# Motor_PowerMosfet.net
KiCad netlist of a schematic drawn in Altium Designer
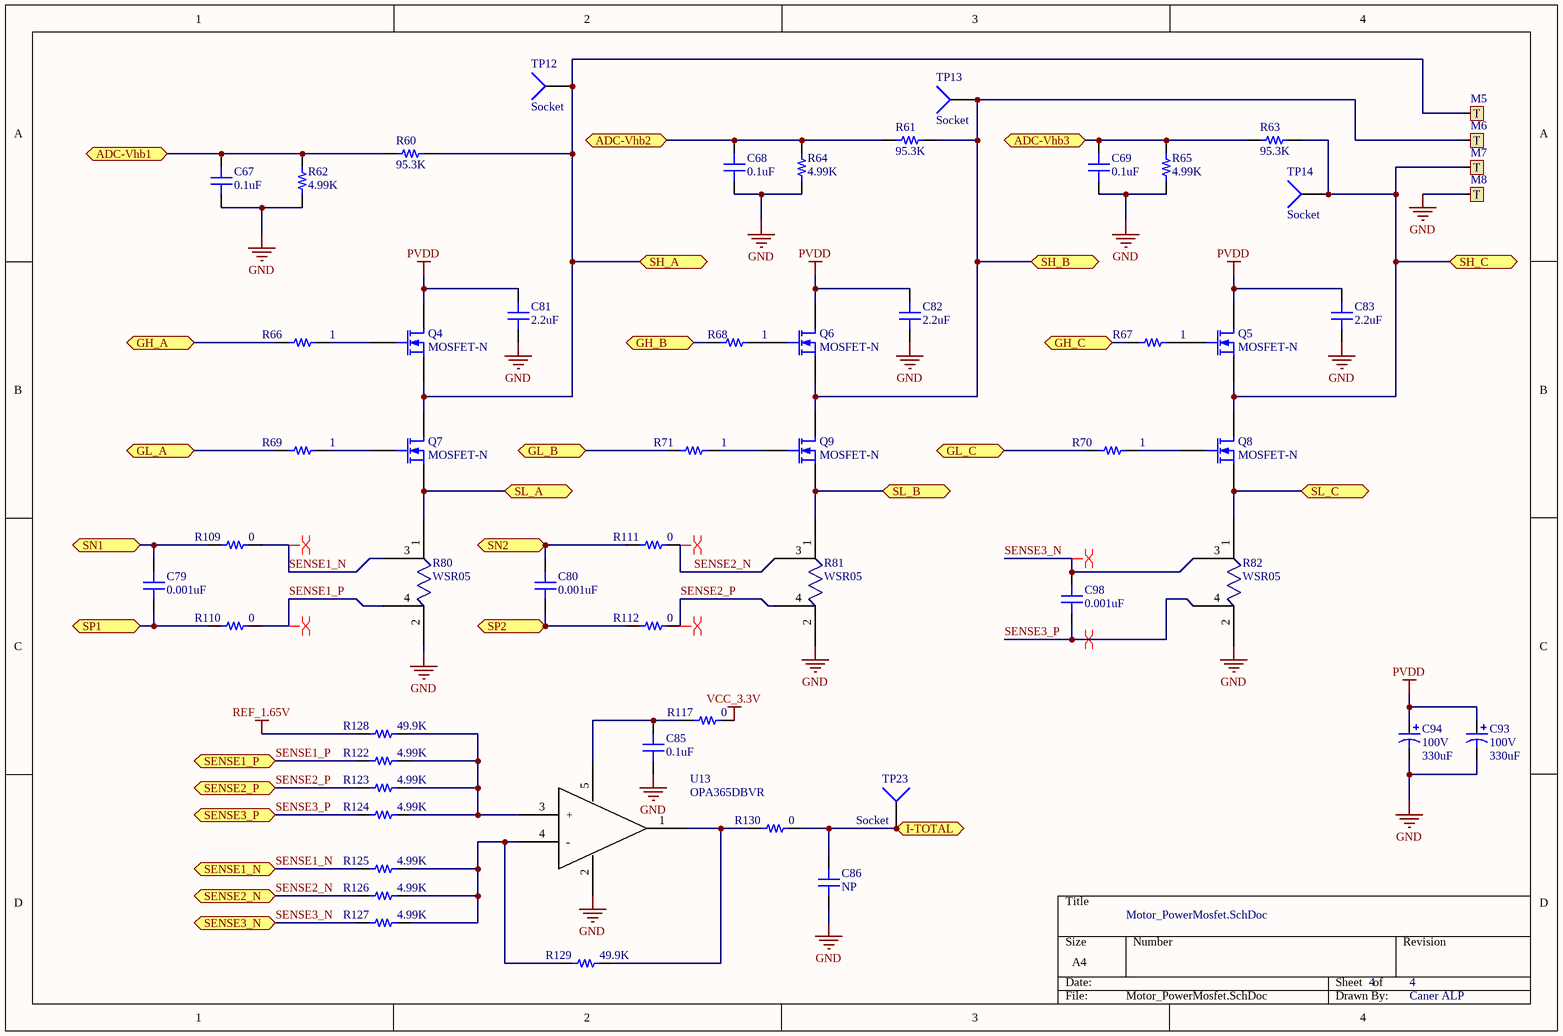
[diagram p0: Motor_PowerMosfet.SchDoc]

(export (version "E")
  (design (tool "Eeschema 10.0.6"))
  (components
    (comp (ref "C67")
      (value "0.1uF")
      (footprint "CAP 0603/1608")
      (description "CAP CER 0.1UF 16V X7R 0603")
      (fields (field (name "PART NUMBER") "CC0603KPX7R7BB104") (field (name "MANUFACTURER") "Yageo"))
      (libsource (lib "Celestial Library Database") (part "Capacitor"))
    )
    (comp (ref "C68")
      (value "0.1uF")
      (footprint "CAP 0603/1608")
      (description "CAP CER 0.1UF 16V X7R 0603")
      (fields (field (name "PART NUMBER") "CC0603KPX7R7BB104") (field (name "MANUFACTURER") "Yageo"))
      (libsource (lib "Celestial Library Database") (part "Capacitor"))
    )
    (comp (ref "C69")
      (value "0.1uF")
      (footprint "CAP 0603/1608")
      (description "CAP CER 0.1UF 16V X7R 0603")
      (fields (field (name "PART NUMBER") "CC0603KPX7R7BB104") (field (name "MANUFACTURER") "Yageo"))
      (libsource (lib "Celestial Library Database") (part "Capacitor"))
    )
    (comp (ref "C79")
      (value "0.001uF")
      (footprint "CAP 0603/1608")
      (description "CAP CER 0.1UF 16V X7R 0603")
      (fields (field (name "PART NUMBER") "CC0603KPX7R7BB104") (field (name "MANUFACTURER") "Yageo"))
      (libsource (lib "Celestial Library Database") (part "Capacitor"))
    )
    (comp (ref "C80")
      (value "0.001uF")
      (footprint "CAP 0603/1608")
      (description "CAP CER 0.1UF 16V X7R 0603")
      (fields (field (name "PART NUMBER") "CC0603KPX7R7BB104") (field (name "MANUFACTURER") "Yageo"))
      (libsource (lib "Celestial Library Database") (part "Capacitor"))
    )
    (comp (ref "C81")
      (value "2.2uF")
      (footprint "CAP 1210/3225 - 2.5MM")
      (description "CAP CER 2.2UF 100V X7R 1210")
      (fields
        (field (name "PART NUMBER") "C3225X7R2A225K230AM")
        (field (name "MANUFACTURER") "TDK Corporation")
      )
      (libsource (lib "Celestial Library Database") (part "Capacitor"))
    )
    (comp (ref "C82")
      (value "2.2uF")
      (footprint "CAP 1210/3225 - 2.5MM")
      (description "CAP CER 2.2UF 100V X7R 1210")
      (fields
        (field (name "PART NUMBER") "C3225X7R2A225K230AM")
        (field (name "MANUFACTURER") "TDK Corporation")
      )
      (libsource (lib "Celestial Library Database") (part "Capacitor"))
    )
    (comp (ref "C83")
      (value "2.2uF")
      (footprint "CAP 1210/3225 - 2.5MM")
      (description "CAP CER 2.2UF 100V X7R 1210")
      (fields
        (field (name "PART NUMBER") "C3225X7R2A225K230AM")
        (field (name "MANUFACTURER") "TDK Corporation")
      )
      (libsource (lib "Celestial Library Database") (part "Capacitor"))
    )
    (comp (ref "C85")
      (value "0.1uF")
      (footprint "CAP 0603/1608")
      (description "CAP CER 0.1UF 16V X7R 0603")
      (fields (field (name "PART NUMBER") "CC0603KPX7R7BB104") (field (name "MANUFACTURER") "Yageo"))
      (libsource (lib "Celestial Library Database") (part "Capacitor"))
    )
    (comp (ref "C86")
      (value "NP")
      (footprint "CAP 0603/1608")
      (description "CAP CER 0.1UF 16V X7R 0603")
      (fields (field (name "PART NUMBER") "CC0603KPX7R7BB104") (field (name "MANUFACTURER") "Yageo"))
      (libsource (lib "Celestial Library Database") (part "Capacitor"))
    )
    (comp (ref "C93")
      (value "100V")
      (footprint "RB7.6-15")
      (description "Polarized Capacitor (Radial)")
      (fields (field (name "ALTIUM_VALUE") "330uF") (field (name "PUBLISHER") "Altium Limited"))
      (libsource (lib "Miscellaneous Devices") (part "Cap Pol1"))
    )
    (comp (ref "C94")
      (value "100V")
      (footprint "RB7.6-15")
      (description "Polarized Capacitor (Radial)")
      (fields (field (name "ALTIUM_VALUE") "330uF") (field (name "PUBLISHER") "Altium Limited"))
      (libsource (lib "Miscellaneous Devices") (part "Cap Pol1"))
    )
    (comp (ref "C98")
      (value "0.001uF")
      (footprint "CAP 0603/1608")
      (description "CAP CER 0.1UF 16V X7R 0603")
      (fields (field (name "PART NUMBER") "CC0603KPX7R7BB104") (field (name "MANUFACTURER") "Yageo"))
      (libsource (lib "Celestial Library Database") (part "Capacitor"))
    )
    (comp (ref "M5") (value "Conn") (footprint "M5 Nut") (libsource (lib "Altium Component") (part "1 Conn")))
    (comp (ref "M6") (value "Conn") (footprint "M5 Nut") (libsource (lib "Altium Component") (part "1 Conn")))
    (comp (ref "M7") (value "Conn") (footprint "M5 Nut") (libsource (lib "Altium Component") (part "1 Conn")))
    (comp (ref "M8") (value "Conn") (footprint "M5 Nut") (libsource (lib "Altium Component") (part "1 Conn")))
    (comp (ref "Q4")
      (value "MOSFET-N")
      (footprint "TO263")
      (description "N-Channel MOSFET")
      (fields (field (name "PUBLISHER") "Altium Limited"))
      (libsource (lib "Miscellaneous Devices") (part "MOSFET-N"))
    )
    (comp (ref "Q5")
      (value "MOSFET-N")
      (footprint "TO263")
      (description "N-Channel MOSFET")
      (fields (field (name "PUBLISHER") "Altium Limited"))
      (libsource (lib "Miscellaneous Devices") (part "MOSFET-N"))
    )
    (comp (ref "Q6")
      (value "MOSFET-N")
      (footprint "TO263")
      (description "N-Channel MOSFET")
      (fields (field (name "PUBLISHER") "Altium Limited"))
      (libsource (lib "Miscellaneous Devices") (part "MOSFET-N"))
    )
    (comp (ref "Q7")
      (value "MOSFET-N")
      (footprint "TO263")
      (description "N-Channel MOSFET")
      (fields (field (name "PUBLISHER") "Altium Limited"))
      (libsource (lib "Miscellaneous Devices") (part "MOSFET-N"))
    )
    (comp (ref "Q8")
      (value "MOSFET-N")
      (footprint "TO263")
      (description "N-Channel MOSFET")
      (fields (field (name "PUBLISHER") "Altium Limited"))
      (libsource (lib "Miscellaneous Devices") (part "MOSFET-N"))
    )
    (comp (ref "Q9")
      (value "MOSFET-N")
      (footprint "TO263")
      (description "N-Channel MOSFET")
      (fields (field (name "PUBLISHER") "Altium Limited"))
      (libsource (lib "Miscellaneous Devices") (part "MOSFET-N"))
    )
    (comp (ref "R60")
      (value "95.3K")
      (footprint "RES 0603/1608")
      (description "RES SMD 330 OHM 5% 1/10W 0603")
      (fields
        (field (name "PART NUMBER") "ERJ-3GEYJ331V")
        (field (name "MANUFACTURER") "Panasonic Electronic Components")
      )
      (libsource (lib "Celestial Library Database") (part "Resistor"))
    )
    (comp (ref "R61")
      (value "95.3K")
      (footprint "RES 0603/1608")
      (description "RES SMD 330 OHM 5% 1/10W 0603")
      (fields
        (field (name "PART NUMBER") "ERJ-3GEYJ331V")
        (field (name "MANUFACTURER") "Panasonic Electronic Components")
      )
      (libsource (lib "Celestial Library Database") (part "Resistor"))
    )
    (comp (ref "R62")
      (value "4.99K")
      (footprint "RES 0603/1608")
      (description "RES SMD 330 OHM 5% 1/10W 0603")
      (fields
        (field (name "PART NUMBER") "ERJ-3GEYJ331V")
        (field (name "MANUFACTURER") "Panasonic Electronic Components")
      )
      (libsource (lib "Celestial Library Database") (part "Resistor"))
    )
    (comp (ref "R63")
      (value "95.3K")
      (footprint "RES 0603/1608")
      (description "RES SMD 330 OHM 5% 1/10W 0603")
      (fields
        (field (name "PART NUMBER") "ERJ-3GEYJ331V")
        (field (name "MANUFACTURER") "Panasonic Electronic Components")
      )
      (libsource (lib "Celestial Library Database") (part "Resistor"))
    )
    (comp (ref "R64")
      (value "4.99K")
      (footprint "RES 0603/1608")
      (description "RES SMD 330 OHM 5% 1/10W 0603")
      (fields
        (field (name "PART NUMBER") "ERJ-3GEYJ331V")
        (field (name "MANUFACTURER") "Panasonic Electronic Components")
      )
      (libsource (lib "Celestial Library Database") (part "Resistor"))
    )
    (comp (ref "R65")
      (value "4.99K")
      (footprint "RES 0603/1608")
      (description "RES SMD 330 OHM 5% 1/10W 0603")
      (fields
        (field (name "PART NUMBER") "ERJ-3GEYJ331V")
        (field (name "MANUFACTURER") "Panasonic Electronic Components")
      )
      (libsource (lib "Celestial Library Database") (part "Resistor"))
    )
    (comp (ref "R66")
      (value "1")
      (footprint "RES 0603/1608")
      (description "RES SMD 330 OHM 5% 1/10W 0603")
      (fields
        (field (name "PART NUMBER") "ERJ-3GEYJ331V")
        (field (name "MANUFACTURER") "Panasonic Electronic Components")
      )
      (libsource (lib "Celestial Library Database") (part "Resistor"))
    )
    (comp (ref "R67")
      (value "1")
      (footprint "RES 0603/1608")
      (description "RES SMD 330 OHM 5% 1/10W 0603")
      (fields
        (field (name "PART NUMBER") "ERJ-3GEYJ331V")
        (field (name "MANUFACTURER") "Panasonic Electronic Components")
      )
      (libsource (lib "Celestial Library Database") (part "Resistor"))
    )
    (comp (ref "R68")
      (value "1")
      (footprint "RES 0603/1608")
      (description "RES SMD 330 OHM 5% 1/10W 0603")
      (fields
        (field (name "PART NUMBER") "ERJ-3GEYJ331V")
        (field (name "MANUFACTURER") "Panasonic Electronic Components")
      )
      (libsource (lib "Celestial Library Database") (part "Resistor"))
    )
    (comp (ref "R69")
      (value "1")
      (footprint "RES 0603/1608")
      (description "RES SMD 330 OHM 5% 1/10W 0603")
      (fields
        (field (name "PART NUMBER") "ERJ-3GEYJ331V")
        (field (name "MANUFACTURER") "Panasonic Electronic Components")
      )
      (libsource (lib "Celestial Library Database") (part "Resistor"))
    )
    (comp (ref "R70")
      (value "1")
      (footprint "RES 0603/1608")
      (description "RES SMD 330 OHM 5% 1/10W 0603")
      (fields
        (field (name "PART NUMBER") "ERJ-3GEYJ331V")
        (field (name "MANUFACTURER") "Panasonic Electronic Components")
      )
      (libsource (lib "Celestial Library Database") (part "Resistor"))
    )
    (comp (ref "R71")
      (value "1")
      (footprint "RES 0603/1608")
      (description "RES SMD 330 OHM 5% 1/10W 0603")
      (fields
        (field (name "PART NUMBER") "ERJ-3GEYJ331V")
        (field (name "MANUFACTURER") "Panasonic Electronic Components")
      )
      (libsource (lib "Celestial Library Database") (part "Resistor"))
    )
    (comp (ref "R80") (value "WSR05") (footprint "RES") (libsource (lib "Altium Component") (part "WSR05")))
    (comp (ref "R81") (value "WSR05") (footprint "RES") (libsource (lib "Altium Component") (part "WSR05")))
    (comp (ref "R82") (value "WSR05") (footprint "RES") (libsource (lib "Altium Component") (part "WSR05")))
    (comp (ref "R109")
      (value "0")
      (footprint "RES 0603/1608")
      (description "RES SMD 330 OHM 5% 1/10W 0603")
      (fields
        (field (name "PART NUMBER") "ERJ-3GEYJ331V")
        (field (name "MANUFACTURER") "Panasonic Electronic Components")
      )
      (libsource (lib "Celestial Library Database") (part "Resistor"))
    )
    (comp (ref "R110")
      (value "0")
      (footprint "RES 0603/1608")
      (description "RES SMD 330 OHM 5% 1/10W 0603")
      (fields
        (field (name "PART NUMBER") "ERJ-3GEYJ331V")
        (field (name "MANUFACTURER") "Panasonic Electronic Components")
      )
      (libsource (lib "Celestial Library Database") (part "Resistor"))
    )
    (comp (ref "R111")
      (value "0")
      (footprint "RES 0603/1608")
      (description "RES SMD 330 OHM 5% 1/10W 0603")
      (fields
        (field (name "PART NUMBER") "ERJ-3GEYJ331V")
        (field (name "MANUFACTURER") "Panasonic Electronic Components")
      )
      (libsource (lib "Celestial Library Database") (part "Resistor"))
    )
    (comp (ref "R112")
      (value "0")
      (footprint "RES 0603/1608")
      (description "RES SMD 330 OHM 5% 1/10W 0603")
      (fields
        (field (name "PART NUMBER") "ERJ-3GEYJ331V")
        (field (name "MANUFACTURER") "Panasonic Electronic Components")
      )
      (libsource (lib "Celestial Library Database") (part "Resistor"))
    )
    (comp (ref "R117")
      (value "0")
      (footprint "RES 0603/1608")
      (description "RES SMD 330 OHM 5% 1/10W 0603")
      (fields
        (field (name "PART NUMBER") "ERJ-3GEYJ331V")
        (field (name "MANUFACTURER") "Panasonic Electronic Components")
      )
      (libsource (lib "Celestial Library Database") (part "Resistor"))
    )
    (comp (ref "R122")
      (value "4.99K")
      (footprint "RES 0603/1608")
      (description "RES SMD 330 OHM 5% 1/10W 0603")
      (fields
        (field (name "PART NUMBER") "ERJ-3GEYJ331V")
        (field (name "MANUFACTURER") "Panasonic Electronic Components")
      )
      (libsource (lib "Celestial Library Database") (part "Resistor"))
    )
    (comp (ref "R123")
      (value "4.99K")
      (footprint "RES 0603/1608")
      (description "RES SMD 330 OHM 5% 1/10W 0603")
      (fields
        (field (name "PART NUMBER") "ERJ-3GEYJ331V")
        (field (name "MANUFACTURER") "Panasonic Electronic Components")
      )
      (libsource (lib "Celestial Library Database") (part "Resistor"))
    )
    (comp (ref "R124")
      (value "4.99K")
      (footprint "RES 0603/1608")
      (description "RES SMD 330 OHM 5% 1/10W 0603")
      (fields
        (field (name "PART NUMBER") "ERJ-3GEYJ331V")
        (field (name "MANUFACTURER") "Panasonic Electronic Components")
      )
      (libsource (lib "Celestial Library Database") (part "Resistor"))
    )
    (comp (ref "R125")
      (value "4.99K")
      (footprint "RES 0603/1608")
      (description "RES SMD 330 OHM 5% 1/10W 0603")
      (fields
        (field (name "PART NUMBER") "ERJ-3GEYJ331V")
        (field (name "MANUFACTURER") "Panasonic Electronic Components")
      )
      (libsource (lib "Celestial Library Database") (part "Resistor"))
    )
    (comp (ref "R126")
      (value "4.99K")
      (footprint "RES 0603/1608")
      (description "RES SMD 330 OHM 5% 1/10W 0603")
      (fields
        (field (name "PART NUMBER") "ERJ-3GEYJ331V")
        (field (name "MANUFACTURER") "Panasonic Electronic Components")
      )
      (libsource (lib "Celestial Library Database") (part "Resistor"))
    )
    (comp (ref "R127")
      (value "4.99K")
      (footprint "RES 0603/1608")
      (description "RES SMD 330 OHM 5% 1/10W 0603")
      (fields
        (field (name "PART NUMBER") "ERJ-3GEYJ331V")
        (field (name "MANUFACTURER") "Panasonic Electronic Components")
      )
      (libsource (lib "Celestial Library Database") (part "Resistor"))
    )
    (comp (ref "R128")
      (value "49.9K")
      (footprint "RES 0603/1608")
      (description "RES SMD 330 OHM 5% 1/10W 0603")
      (fields
        (field (name "PART NUMBER") "ERJ-3GEYJ331V")
        (field (name "MANUFACTURER") "Panasonic Electronic Components")
      )
      (libsource (lib "Celestial Library Database") (part "Resistor"))
    )
    (comp (ref "R129")
      (value "49.9K")
      (footprint "RES 0603/1608")
      (description "RES SMD 330 OHM 5% 1/10W 0603")
      (fields
        (field (name "PART NUMBER") "ERJ-3GEYJ331V")
        (field (name "MANUFACTURER") "Panasonic Electronic Components")
      )
      (libsource (lib "Celestial Library Database") (part "Resistor"))
    )
    (comp (ref "R130")
      (value "0")
      (footprint "RES 0603/1608")
      (description "RES SMD 330 OHM 5% 1/10W 0603")
      (fields
        (field (name "PART NUMBER") "ERJ-3GEYJ331V")
        (field (name "MANUFACTURER") "Panasonic Electronic Components")
      )
      (libsource (lib "Celestial Library Database") (part "Resistor"))
    )
    (comp (ref "TP12")
      (value "Socket")
      (footprint "PIN1")
      (fields (field (name "PUBLISHER") "Altium Limited"))
      (libsource (lib "Miscellaneous Connectors") (part "Socket"))
    )
    (comp (ref "TP13")
      (value "Socket")
      (footprint "PIN1")
      (fields (field (name "PUBLISHER") "Altium Limited"))
      (libsource (lib "Miscellaneous Connectors") (part "Socket"))
    )
    (comp (ref "TP14")
      (value "Socket")
      (footprint "PIN1")
      (fields (field (name "PUBLISHER") "Altium Limited"))
      (libsource (lib "Miscellaneous Connectors") (part "Socket"))
    )
    (comp (ref "TP23")
      (value "Socket")
      (footprint "PIN1")
      (fields (field (name "PUBLISHER") "Altium Limited"))
      (libsource (lib "Miscellaneous Connectors") (part "Socket"))
    )
    (comp (ref "U13")
      (value "OPA365DBVR")
      (footprint "DBV005")
      (libsource (lib "Altium Component") (part "TLV2781DBVR"))
    )
  )
  (nets
    (net (code "1") (name "/ADC-Vhb1") (class "Default")
      (node (ref "C67") (pin "2") (pinfunction "2_2") (pintype "passive"))
      (node (ref "R60") (pin "2") (pinfunction "2_2") (pintype "passive"))
      (node (ref "R62") (pin "2") (pinfunction "2_2") (pintype "passive"))
    )
    (net (code "2") (name "/ADC-Vhb2") (class "Default")
      (node (ref "C68") (pin "2") (pinfunction "2_2") (pintype "passive"))
      (node (ref "R61") (pin "2") (pinfunction "2_2") (pintype "passive"))
      (node (ref "R64") (pin "2") (pinfunction "2_2") (pintype "passive"))
    )
    (net (code "3") (name "/ADC-Vhb3") (class "Default")
      (node (ref "C69") (pin "2") (pinfunction "2_2") (pintype "passive"))
      (node (ref "R63") (pin "2") (pinfunction "2_2") (pintype "passive"))
      (node (ref "R65") (pin "2") (pinfunction "2_2") (pintype "passive"))
    )
    (net (code "4") (name "/GH_A") (class "Default")
      (node (ref "R66") (pin "2") (pinfunction "2_2") (pintype "passive"))
    )
    (net (code "5") (name "/GH_B") (class "Default")
      (node (ref "R68") (pin "2") (pinfunction "2_2") (pintype "passive"))
    )
    (net (code "6") (name "/GH_C") (class "Default")
      (node (ref "R67") (pin "2") (pinfunction "2_2") (pintype "passive"))
    )
    (net (code "7") (name "/GL_A") (class "Default")
      (node (ref "R69") (pin "2") (pinfunction "2_2") (pintype "passive"))
    )
    (net (code "8") (name "/GL_B") (class "Default")
      (node (ref "R71") (pin "2") (pinfunction "2_2") (pintype "passive"))
    )
    (net (code "9") (name "/GL_C") (class "Default")
      (node (ref "R70") (pin "2") (pinfunction "2_2") (pintype "passive"))
    )
    (net (code "10") (name "/I-TOTAL") (class "Default")
      (node (ref "C86") (pin "2") (pinfunction "2_2") (pintype "passive"))
      (node (ref "R130") (pin "1") (pinfunction "1_1") (pintype "passive"))
      (node (ref "TP23") (pin "1") (pinfunction "1_1") (pintype "passive"))
    )
    (net (code "11") (name "/SENSE1_N") (class "Default")
      (node (ref "R109") (pin "1") (pinfunction "1_1") (pintype "passive"))
      (node (ref "R125") (pin "2") (pinfunction "2_2") (pintype "passive"))
      (node (ref "R80") (pin "3") (pinfunction "3_3") (pintype "passive"))
    )
    (net (code "12") (name "/SENSE1_P") (class "Default")
      (node (ref "R110") (pin "1") (pinfunction "1_1") (pintype "passive"))
      (node (ref "R122") (pin "2") (pinfunction "2_2") (pintype "passive"))
      (node (ref "R80") (pin "4") (pinfunction "4_4") (pintype "passive"))
    )
    (net (code "13") (name "/SENSE2_N") (class "Default")
      (node (ref "R111") (pin "1") (pinfunction "1_1") (pintype "passive"))
      (node (ref "R126") (pin "2") (pinfunction "2_2") (pintype "passive"))
      (node (ref "R81") (pin "3") (pinfunction "3_3") (pintype "passive"))
    )
    (net (code "14") (name "/SENSE2_P") (class "Default")
      (node (ref "R112") (pin "1") (pinfunction "1_1") (pintype "passive"))
      (node (ref "R123") (pin "2") (pinfunction "2_2") (pintype "passive"))
      (node (ref "R81") (pin "4") (pinfunction "4_4") (pintype "passive"))
    )
    (net (code "15") (name "/SENSE3_N") (class "Default")
      (node (ref "C98") (pin "2") (pinfunction "2_2") (pintype "passive"))
      (node (ref "R127") (pin "2") (pinfunction "2_2") (pintype "passive"))
      (node (ref "R82") (pin "3") (pinfunction "3_3") (pintype "passive"))
    )
    (net (code "16") (name "/SENSE3_P") (class "Default")
      (node (ref "C98") (pin "1") (pinfunction "1_1") (pintype "passive"))
      (node (ref "R124") (pin "2") (pinfunction "2_2") (pintype "passive"))
      (node (ref "R82") (pin "4") (pinfunction "4_4") (pintype "passive"))
    )
    (net (code "17") (name "/SH_A") (class "Default")
      (node (ref "M5") (pin "1") (pinfunction "T_1") (pintype "passive"))
      (node (ref "Q4") (pin "3") (pinfunction "S_3") (pintype "passive"))
      (node (ref "Q7") (pin "1") (pinfunction "D_1") (pintype "passive"))
      (node (ref "R60") (pin "1") (pinfunction "1_1") (pintype "passive"))
      (node (ref "TP12") (pin "1") (pinfunction "1_1") (pintype "passive"))
    )
    (net (code "18") (name "/SH_B") (class "Default")
      (node (ref "M6") (pin "1") (pinfunction "T_1") (pintype "passive"))
      (node (ref "Q6") (pin "3") (pinfunction "S_3") (pintype "passive"))
      (node (ref "Q9") (pin "1") (pinfunction "D_1") (pintype "passive"))
      (node (ref "R61") (pin "1") (pinfunction "1_1") (pintype "passive"))
      (node (ref "TP13") (pin "1") (pinfunction "1_1") (pintype "passive"))
    )
    (net (code "19") (name "/SH_C") (class "Default")
      (node (ref "M7") (pin "1") (pinfunction "T_1") (pintype "passive"))
      (node (ref "Q5") (pin "3") (pinfunction "S_3") (pintype "passive"))
      (node (ref "Q8") (pin "1") (pinfunction "D_1") (pintype "passive"))
      (node (ref "R63") (pin "1") (pinfunction "1_1") (pintype "passive"))
      (node (ref "TP14") (pin "1") (pinfunction "1_1") (pintype "passive"))
    )
    (net (code "20") (name "/SL_A") (class "Default")
      (node (ref "Q7") (pin "3") (pinfunction "S_3") (pintype "passive"))
      (node (ref "R80") (pin "1") (pinfunction "1_1") (pintype "passive"))
    )
    (net (code "21") (name "/SL_B") (class "Default")
      (node (ref "Q9") (pin "3") (pinfunction "S_3") (pintype "passive"))
      (node (ref "R81") (pin "1") (pinfunction "1_1") (pintype "passive"))
    )
    (net (code "22") (name "/SL_C") (class "Default")
      (node (ref "Q8") (pin "3") (pinfunction "S_3") (pintype "passive"))
      (node (ref "R82") (pin "1") (pinfunction "1_1") (pintype "passive"))
    )
    (net (code "23") (name "/SN1") (class "Default")
      (node (ref "C79") (pin "2") (pinfunction "2_2") (pintype "passive"))
      (node (ref "R109") (pin "2") (pinfunction "2_2") (pintype "passive"))
    )
    (net (code "24") (name "/SN2") (class "Default")
      (node (ref "C80") (pin "2") (pinfunction "2_2") (pintype "passive"))
      (node (ref "R111") (pin "2") (pinfunction "2_2") (pintype "passive"))
    )
    (net (code "25") (name "/SP1") (class "Default")
      (node (ref "C79") (pin "1") (pinfunction "1_1") (pintype "passive"))
      (node (ref "R110") (pin "2") (pinfunction "2_2") (pintype "passive"))
    )
    (net (code "26") (name "/SP2") (class "Default")
      (node (ref "C80") (pin "1") (pinfunction "1_1") (pintype "passive"))
      (node (ref "R112") (pin "2") (pinfunction "2_2") (pintype "passive"))
    )
    (net (code "27") (name "GND") (class "Default")
      (node (ref "C67") (pin "1") (pinfunction "1_1") (pintype "passive"))
      (node (ref "C68") (pin "1") (pinfunction "1_1") (pintype "passive"))
      (node (ref "C69") (pin "1") (pinfunction "1_1") (pintype "passive"))
      (node (ref "C81") (pin "1") (pinfunction "1_1") (pintype "passive"))
      (node (ref "C82") (pin "1") (pinfunction "1_1") (pintype "passive"))
      (node (ref "C83") (pin "1") (pinfunction "1_1") (pintype "passive"))
      (node (ref "C85") (pin "1") (pinfunction "1_1") (pintype "passive"))
      (node (ref "C86") (pin "1") (pinfunction "1_1") (pintype "passive"))
      (node (ref "C93") (pin "2") (pinfunction "2_2") (pintype "passive"))
      (node (ref "C94") (pin "2") (pinfunction "2_2") (pintype "passive"))
      (node (ref "M8") (pin "1") (pinfunction "T_1") (pintype "passive"))
      (node (ref "R62") (pin "1") (pinfunction "1_1") (pintype "passive"))
      (node (ref "R64") (pin "1") (pinfunction "1_1") (pintype "passive"))
      (node (ref "R65") (pin "1") (pinfunction "1_1") (pintype "passive"))
      (node (ref "R80") (pin "2") (pinfunction "2_2") (pintype "passive"))
      (node (ref "R81") (pin "2") (pinfunction "2_2") (pintype "passive"))
      (node (ref "R82") (pin "2") (pinfunction "2_2") (pintype "passive"))
      (node (ref "U13") (pin "2") (pinfunction "2_2") (pintype "passive"))
    )
    (net (code "28") (name "Net-(C85-Pad2)") (class "Default")
      (node (ref "C85") (pin "2") (pinfunction "2_2") (pintype "passive"))
      (node (ref "R117") (pin "2") (pinfunction "2_2") (pintype "passive"))
      (node (ref "U13") (pin "5") (pinfunction "5_5") (pintype "passive"))
    )
    (net (code "29") (name "Net-(Q4-G)") (class "Default")
      (node (ref "Q4") (pin "2") (pinfunction "G_2") (pintype "passive"))
      (node (ref "R66") (pin "1") (pinfunction "1_1") (pintype "passive"))
    )
    (net (code "30") (name "Net-(Q5-G)") (class "Default")
      (node (ref "Q5") (pin "2") (pinfunction "G_2") (pintype "passive"))
      (node (ref "R67") (pin "1") (pinfunction "1_1") (pintype "passive"))
    )
    (net (code "31") (name "Net-(Q6-G)") (class "Default")
      (node (ref "Q6") (pin "2") (pinfunction "G_2") (pintype "passive"))
      (node (ref "R68") (pin "1") (pinfunction "1_1") (pintype "passive"))
    )
    (net (code "32") (name "Net-(Q7-G)") (class "Default")
      (node (ref "Q7") (pin "2") (pinfunction "G_2") (pintype "passive"))
      (node (ref "R69") (pin "1") (pinfunction "1_1") (pintype "passive"))
    )
    (net (code "33") (name "Net-(Q8-G)") (class "Default")
      (node (ref "Q8") (pin "2") (pinfunction "G_2") (pintype "passive"))
      (node (ref "R70") (pin "1") (pinfunction "1_1") (pintype "passive"))
    )
    (net (code "34") (name "Net-(Q9-G)") (class "Default")
      (node (ref "Q9") (pin "2") (pinfunction "G_2") (pintype "passive"))
      (node (ref "R71") (pin "1") (pinfunction "1_1") (pintype "passive"))
    )
    (net (code "35") (name "Net-(R129-Pad1)") (class "Default")
      (node (ref "R129") (pin "1") (pinfunction "1_1") (pintype "passive"))
      (node (ref "R130") (pin "2") (pinfunction "2_2") (pintype "passive"))
      (node (ref "U13") (pin "1") (pinfunction "1_1") (pintype "passive"))
    )
    (net (code "36") (name "Net-(U13-+)") (class "Default")
      (node (ref "R122") (pin "1") (pinfunction "1_1") (pintype "passive"))
      (node (ref "R123") (pin "1") (pinfunction "1_1") (pintype "passive"))
      (node (ref "R124") (pin "1") (pinfunction "1_1") (pintype "passive"))
      (node (ref "R128") (pin "1") (pinfunction "1_1") (pintype "passive"))
      (node (ref "U13") (pin "3") (pinfunction "+_3") (pintype "passive"))
    )
    (net (code "37") (name "Net-(U13--)") (class "Default")
      (node (ref "R125") (pin "1") (pinfunction "1_1") (pintype "passive"))
      (node (ref "R126") (pin "1") (pinfunction "1_1") (pintype "passive"))
      (node (ref "R127") (pin "1") (pinfunction "1_1") (pintype "passive"))
      (node (ref "R129") (pin "2") (pinfunction "2_2") (pintype "passive"))
      (node (ref "U13") (pin "4") (pinfunction "-_4") (pintype "passive"))
    )
    (net (code "38") (name "PVDD") (class "Default")
      (node (ref "C81") (pin "2") (pinfunction "2_2") (pintype "passive"))
      (node (ref "C82") (pin "2") (pinfunction "2_2") (pintype "passive"))
      (node (ref "C83") (pin "2") (pinfunction "2_2") (pintype "passive"))
      (node (ref "C93") (pin "1") (pinfunction "1_1") (pintype "passive"))
      (node (ref "C94") (pin "1") (pinfunction "1_1") (pintype "passive"))
      (node (ref "Q4") (pin "1") (pinfunction "D_1") (pintype "passive"))
      (node (ref "Q5") (pin "1") (pinfunction "D_1") (pintype "passive"))
      (node (ref "Q6") (pin "1") (pinfunction "D_1") (pintype "passive"))
    )
    (net (code "39") (name "REF_1.65V") (class "Default")
      (node (ref "R128") (pin "2") (pinfunction "2_2") (pintype "passive"))
    )
    (net (code "40") (name "VCC_3.3V") (class "Default")
      (node (ref "R117") (pin "1") (pinfunction "1_1") (pintype "passive"))
    )
  )
)
